# 2020_Circuit_Example_ArduinoUno_Version_.net
KiCad netlist of a schematic drawn in EAGLE
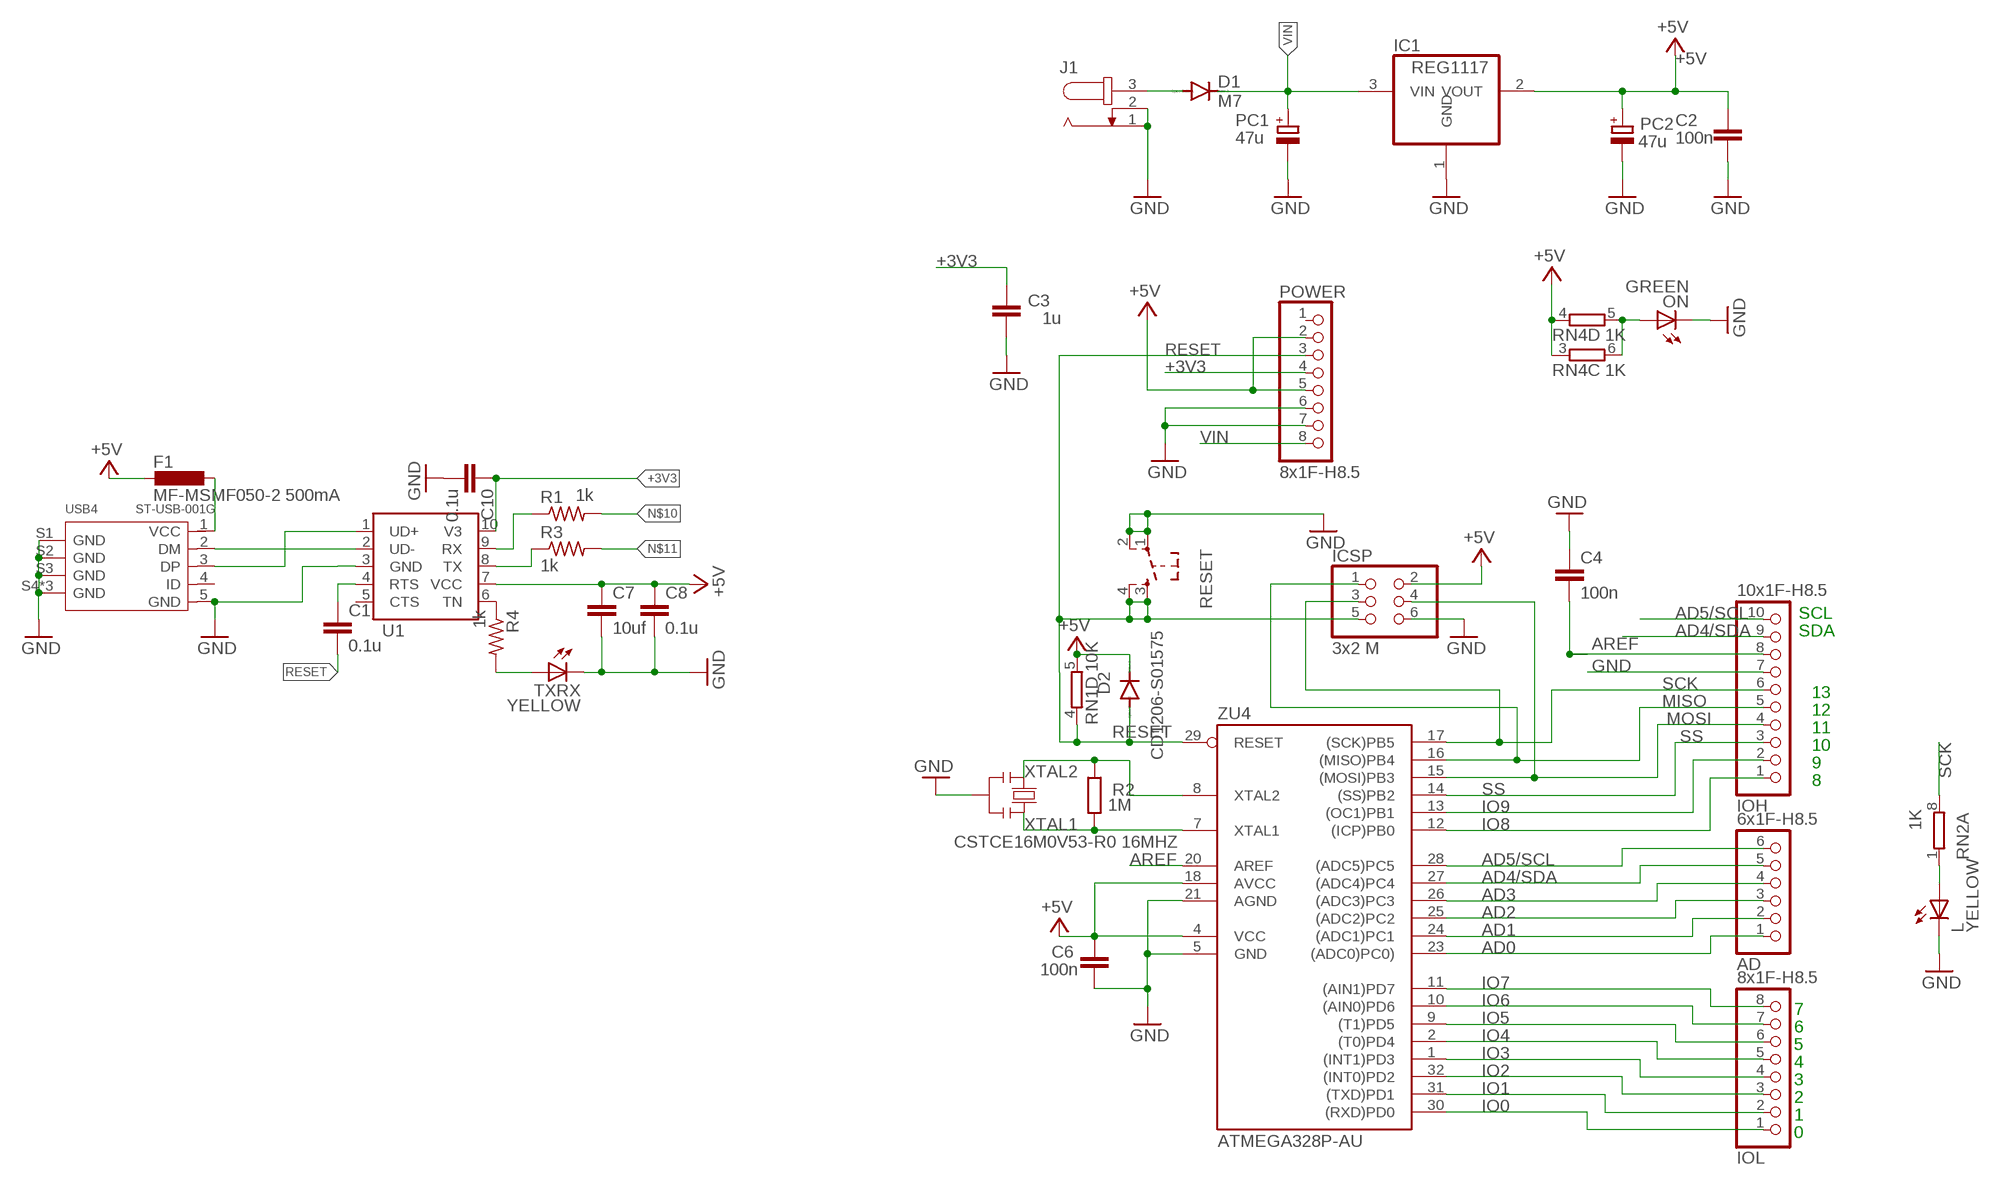
[diagram p0: schematic, sheet 1]

(export (version "E")
  (design (tool "Eeschema 10.0.6"))
  (components
    (comp (ref "AD")
      (value "6x1F-H8.5")
      (footprint "eagle-import:1X06")
      (libsource (lib "eagle-import") (part "PINHD-1X6"))
    )
    (comp (ref "C1")
      (value "0.1u")
      (footprint "eagle-import:C0805")
      (libsource (lib "eagle-import") (part "rcl_C-EUC0805"))
    )
    (comp (ref "C2")
      (value "100n")
      (footprint "eagle-import:C0603-ROUND")
      (libsource (lib "eagle-import") (part "C-EU0603-RND"))
    )
    (comp (ref "C3")
      (value "1u")
      (footprint "eagle-import:C0603-ROUND")
      (libsource (lib "eagle-import") (part "C-EU0603-RND"))
    )
    (comp (ref "C4")
      (value "100n")
      (footprint "eagle-import:C0805")
      (libsource (lib "eagle-import") (part "rcl_C-EUC0805"))
    )
    (comp (ref "C6")
      (value "100n")
      (footprint "eagle-import:C0603-ROUND")
      (libsource (lib "eagle-import") (part "C-EU0603-RND"))
    )
    (comp (ref "C7")
      (value "10uf")
      (footprint "eagle-import:C0805")
      (libsource (lib "eagle-import") (part "rcl_C-EUC0805"))
    )
    (comp (ref "C8")
      (value "0.1u")
      (footprint "eagle-import:C0805")
      (libsource (lib "eagle-import") (part "rcl_C-EUC0805"))
    )
    (comp (ref "C10")
      (value "0.1u")
      (footprint "eagle-import:C0805")
      (libsource (lib "eagle-import") (part "rcl_C-EUC0805"))
    )
    (comp (ref "D1")
      (value "M7")
      (footprint "eagle-import:SMB")
      (libsource (lib "eagle-import") (part "DIODE-SMB"))
    )
    (comp (ref "D2")
      (value "CD1206-S01575")
      (footprint "eagle-import:MINIMELF")
      (libsource (lib "eagle-import") (part "DIODE-MINIMELF"))
    )
    (comp (ref "F1")
      (value "MF-MSMF050-2 500mA")
      (footprint "eagle-import:L1812")
      (libsource (lib "eagle-import") (part "L-EUL1812"))
    )
    (comp (ref "IC1")
      (value "REG1117")
      (footprint "eagle-import:SOT223")
      (libsource (lib "eagle-import") (part "REG1117"))
    )
    (comp (ref "ICSP")
      (value "3x2 M")
      (footprint "eagle-import:2X03")
      (libsource (lib "eagle-import") (part "PINHD-2X3"))
    )
    (comp (ref "IOH")
      (value "10x1F-H8.5")
      (footprint "eagle-import:1X10")
      (libsource (lib "eagle-import") (part "PINHD-1X10_ARD"))
    )
    (comp (ref "IOL")
      (value "8x1F-H8.5")
      (footprint "eagle-import:1X08")
      (libsource (lib "eagle-import") (part "PINHD-1X8"))
    )
    (comp (ref "J1")
      (value "JACK-PLUG0")
      (footprint "eagle-import:SPC4077")
      (libsource (lib "eagle-import") (part "JACK-PLUG0"))
    )
    (comp (ref "L")
      (value "YELLOW")
      (footprint "eagle-import:CHIP-LED0805")
      (libsource (lib "eagle-import") (part "LEDCHIP-LED0805"))
    )
    (comp (ref "ON")
      (value "GREEN")
      (footprint "eagle-import:CHIP-LED0805")
      (libsource (lib "eagle-import") (part "LEDCHIP-LED0805"))
    )
    (comp (ref "PC1")
      (value "47u")
      (footprint "eagle-import:PANASONIC_D")
      (libsource (lib "eagle-import") (part "CPOL-EUD"))
    )
    (comp (ref "PC2")
      (value "47u")
      (footprint "eagle-import:PANASONIC_D")
      (libsource (lib "eagle-import") (part "CPOL-EUD"))
    )
    (comp (ref "POWER")
      (value "8x1F-H8.5")
      (footprint "eagle-import:1X08")
      (libsource (lib "eagle-import") (part "PINHD-1X8"))
    )
    (comp (ref "R1")
      (value "1k")
      (footprint "eagle-import:M0805")
      (libsource (lib "eagle-import") (part "R-US_M0805"))
    )
    (comp (ref "R2")
      (value "1M")
      (footprint "eagle-import:R0603-ROUND")
      (libsource (lib "eagle-import") (part "R-EU_R0603"))
    )
    (comp (ref "R3")
      (value "1k")
      (footprint "eagle-import:M0805")
      (libsource (lib "eagle-import") (part "R-US_M0805"))
    )
    (comp (ref "R4")
      (value "1k")
      (footprint "eagle-import:M0805")
      (libsource (lib "eagle-import") (part "R-US_M0805"))
    )
    (comp (ref "RESET")
      (value "SW_TACT_4P")
      (footprint "eagle-import:SW_TACT_SMALL")
      (libsource (lib "eagle-import") (part "SW_TACT_4P"))
    )
    (comp (ref "RN1")
      (value "10K")
      (footprint "eagle-import:CAY16")
      (libsource (lib "eagle-import") (part "4R-NCAY16"))
    )
    (comp (ref "RN2")
      (value "1K")
      (footprint "eagle-import:CAY16")
      (libsource (lib "eagle-import") (part "4R-NCAY16"))
    )
    (comp (ref "RN4")
      (value "1K")
      (footprint "eagle-import:CAY16")
      (libsource (lib "eagle-import") (part "4R-NCAY16"))
    )
    (comp (ref "TXRX")
      (value "YELLOW")
      (footprint "eagle-import:CHIP-LED0805")
      (libsource (lib "eagle-import") (part "LEDCHIP-LED0805"))
    )
    (comp (ref "U1")
      (value "CH340ESMD")
      (footprint "eagle-import:MSOP10")
      (libsource (lib "eagle-import") (part "CH340ESMD"))
    )
    (comp (ref "USB4")
      (value "ST-USB-001G")
      (footprint "eagle-import:MICRO-USB5+4P-SMD-0.65-B")
      (libsource (lib "eagle-import") (part "MICRO-USB-SMD-B-WITHOUT-POST-W/P(ST-USB-001G)"))
    )
    (comp (ref "Y2")
      (value "CSTCE16M0V53-R0 16MHZ")
      (footprint "eagle-import:RESONATOR")
      (libsource (lib "eagle-import") (part "RESONATORMU"))
    )
    (comp (ref "ZU4")
      (value "ATMEGA328P-AU")
      (footprint "eagle-import:TQFP32-08")
      (libsource (lib "eagle-import") (part "ATMEGA328P-AU"))
    )
  )
  (nets
    (net (code "1") (name "+3V3") (class "Default")
      (node (ref "C10") (pin "1") (pinfunction "1_1") (pintype "passive"))
      (node (ref "C3") (pin "2") (pinfunction "2_2") (pintype "passive"))
      (node (ref "POWER") (pin "4") (pinfunction "4_4") (pintype "passive"))
      (node (ref "U1") (pin "10") (pinfunction "V3_10") (pintype "power_in"))
    )
    (net (code "2") (name "+5V") (class "Default")
      (node (ref "C2") (pin "2") (pinfunction "2_2") (pintype "passive"))
      (node (ref "C6") (pin "2") (pinfunction "2_2") (pintype "passive"))
      (node (ref "C7") (pin "1") (pinfunction "1_1") (pintype "passive"))
      (node (ref "C8") (pin "1") (pinfunction "1_1") (pintype "passive"))
      (node (ref "D2") (pin "C") (pinfunction "C_C") (pintype "passive"))
      (node (ref "F1") (pin "2") (pinfunction "2_2") (pintype "passive"))
      (node (ref "IC1") (pin "2") (pinfunction "VOUT_2") (pintype "output"))
      (node (ref "ICSP") (pin "2") (pinfunction "2_2") (pintype "passive"))
      (node (ref "PC2") (pin "+") (pinfunction "+_+") (pintype "passive"))
      (node (ref "POWER") (pin "2") (pinfunction "2_2") (pintype "passive"))
      (node (ref "POWER") (pin "5") (pinfunction "5_5") (pintype "passive"))
      (node (ref "RN1") (pin "5") (pinfunction "2_5") (pintype "passive"))
      (node (ref "RN4") (pin "3") (pinfunction "1_3") (pintype "passive"))
      (node (ref "RN4") (pin "4") (pinfunction "1_4") (pintype "passive"))
      (node (ref "U1") (pin "7") (pinfunction "VCC_7") (pintype "power_in"))
      (node (ref "ZU4") (pin "18") (pinfunction "AVCC_18") (pintype "power_in"))
      (node (ref "ZU4") (pin "4") (pinfunction "VCC_4") (pintype "power_in"))
    )
    (net (code "3") (name "/AD0") (class "Default")
      (node (ref "AD") (pin "1") (pinfunction "1_1") (pintype "passive"))
      (node (ref "ZU4") (pin "23") (pinfunction "(ADC0)PC0)_23") (pintype "bidirectional"))
    )
    (net (code "4") (name "/AD1") (class "Default")
      (node (ref "AD") (pin "2") (pinfunction "2_2") (pintype "passive"))
      (node (ref "ZU4") (pin "24") (pinfunction "(ADC1)PC1_24") (pintype "bidirectional"))
    )
    (net (code "5") (name "/AD2") (class "Default")
      (node (ref "AD") (pin "3") (pinfunction "3_3") (pintype "passive"))
      (node (ref "ZU4") (pin "25") (pinfunction "(ADC2)PC2_25") (pintype "bidirectional"))
    )
    (net (code "6") (name "/AD3") (class "Default")
      (node (ref "AD") (pin "4") (pinfunction "4_4") (pintype "passive"))
      (node (ref "ZU4") (pin "26") (pinfunction "(ADC3)PC3_26") (pintype "bidirectional"))
    )
    (net (code "7") (name "/AD4{slash}SDA") (class "Default")
      (node (ref "AD") (pin "5") (pinfunction "5_5") (pintype "passive"))
      (node (ref "IOH") (pin "9") (pinfunction "9_9") (pintype "passive"))
      (node (ref "ZU4") (pin "27") (pinfunction "(ADC4)PC4_27") (pintype "bidirectional"))
    )
    (net (code "8") (name "/AD5{slash}SCL") (class "Default")
      (node (ref "AD") (pin "6") (pinfunction "6_6") (pintype "passive"))
      (node (ref "IOH") (pin "10") (pinfunction "10_10") (pintype "passive"))
      (node (ref "ZU4") (pin "28") (pinfunction "(ADC5)PC5_28") (pintype "bidirectional"))
    )
    (net (code "9") (name "/AREF") (class "Default")
      (node (ref "C4") (pin "2") (pinfunction "2_2") (pintype "passive"))
      (node (ref "IOH") (pin "8") (pinfunction "8_8") (pintype "passive"))
      (node (ref "ZU4") (pin "20") (pinfunction "AREF_20") (pintype "passive"))
    )
    (net (code "10") (name "/IO0") (class "Default")
      (node (ref "IOL") (pin "1") (pinfunction "1_1") (pintype "passive"))
      (node (ref "ZU4") (pin "30") (pinfunction "(RXD)PD0_30") (pintype "bidirectional"))
    )
    (net (code "11") (name "/IO1") (class "Default")
      (node (ref "IOL") (pin "2") (pinfunction "2_2") (pintype "passive"))
      (node (ref "ZU4") (pin "31") (pinfunction "(TXD)PD1_31") (pintype "bidirectional"))
    )
    (net (code "12") (name "/IO2") (class "Default")
      (node (ref "IOL") (pin "3") (pinfunction "3_3") (pintype "passive"))
      (node (ref "ZU4") (pin "32") (pinfunction "(INT0)PD2_32") (pintype "bidirectional"))
    )
    (net (code "13") (name "/IO3") (class "Default")
      (node (ref "IOL") (pin "4") (pinfunction "4_4") (pintype "passive"))
      (node (ref "ZU4") (pin "1") (pinfunction "(INT1)PD3_1") (pintype "bidirectional"))
    )
    (net (code "14") (name "/IO4") (class "Default")
      (node (ref "IOL") (pin "5") (pinfunction "5_5") (pintype "passive"))
      (node (ref "ZU4") (pin "2") (pinfunction "(T0)PD4_2") (pintype "bidirectional"))
    )
    (net (code "15") (name "/IO5") (class "Default")
      (node (ref "IOL") (pin "6") (pinfunction "6_6") (pintype "passive"))
      (node (ref "ZU4") (pin "9") (pinfunction "(T1)PD5_9") (pintype "bidirectional"))
    )
    (net (code "16") (name "/IO6") (class "Default")
      (node (ref "IOL") (pin "7") (pinfunction "7_7") (pintype "passive"))
      (node (ref "ZU4") (pin "10") (pinfunction "(AIN0)PD6_10") (pintype "bidirectional"))
    )
    (net (code "17") (name "/IO7") (class "Default")
      (node (ref "IOL") (pin "8") (pinfunction "8_8") (pintype "passive"))
      (node (ref "ZU4") (pin "11") (pinfunction "(AIN1)PD7_11") (pintype "bidirectional"))
    )
    (net (code "18") (name "/IO8") (class "Default")
      (node (ref "IOH") (pin "1") (pinfunction "1_1") (pintype "passive"))
      (node (ref "ZU4") (pin "12") (pinfunction "(ICP)PB0_12") (pintype "bidirectional"))
    )
    (net (code "19") (name "/IO9") (class "Default")
      (node (ref "IOH") (pin "2") (pinfunction "2_2") (pintype "passive"))
      (node (ref "ZU4") (pin "13") (pinfunction "(OC1)PB1_13") (pintype "bidirectional"))
    )
    (net (code "20") (name "/MISO") (class "Default")
      (node (ref "ICSP") (pin "1") (pinfunction "1_1") (pintype "passive"))
      (node (ref "IOH") (pin "5") (pinfunction "5_5") (pintype "passive"))
      (node (ref "ZU4") (pin "16") (pinfunction "(MISO)PB4_16") (pintype "bidirectional"))
    )
    (net (code "21") (name "/MOSI") (class "Default")
      (node (ref "ICSP") (pin "4") (pinfunction "4_4") (pintype "passive"))
      (node (ref "IOH") (pin "4") (pinfunction "4_4") (pintype "passive"))
      (node (ref "ZU4") (pin "15") (pinfunction "(MOSI)PB3_15") (pintype "bidirectional"))
    )
    (net (code "22") (name "/SCK") (class "Default")
      (node (ref "ICSP") (pin "3") (pinfunction "3_3") (pintype "passive"))
      (node (ref "IOH") (pin "6") (pinfunction "6_6") (pintype "passive"))
      (node (ref "RN2") (pin "8") (pinfunction "2_8") (pintype "passive"))
      (node (ref "ZU4") (pin "17") (pinfunction "(SCK)PB5_17") (pintype "bidirectional"))
    )
    (net (code "23") (name "/SS") (class "Default")
      (node (ref "IOH") (pin "3") (pinfunction "3_3") (pintype "passive"))
      (node (ref "ZU4") (pin "14") (pinfunction "(SS)PB2_14") (pintype "bidirectional"))
    )
    (net (code "24") (name "/XTAL1") (class "Default")
      (node (ref "R2") (pin "1") (pinfunction "1_1") (pintype "passive"))
      (node (ref "Y2") (pin "3") (pinfunction "3_3") (pintype "passive"))
      (node (ref "ZU4") (pin "7") (pinfunction "XTAL1_7") (pintype "bidirectional"))
    )
    (net (code "25") (name "/XTAL2") (class "Default")
      (node (ref "R2") (pin "2") (pinfunction "2_2") (pintype "passive"))
      (node (ref "Y2") (pin "1") (pinfunction "1_1") (pintype "passive"))
      (node (ref "ZU4") (pin "8") (pinfunction "XTAL2_8") (pintype "bidirectional"))
    )
    (net (code "26") (name "GND") (class "Default")
      (node (ref "C10") (pin "2") (pinfunction "2_2") (pintype "passive"))
      (node (ref "C2") (pin "1") (pinfunction "1_1") (pintype "passive"))
      (node (ref "C3") (pin "1") (pinfunction "1_1") (pintype "passive"))
      (node (ref "C4") (pin "1") (pinfunction "1_1") (pintype "passive"))
      (node (ref "C6") (pin "1") (pinfunction "1_1") (pintype "passive"))
      (node (ref "C7") (pin "2") (pinfunction "2_2") (pintype "passive"))
      (node (ref "C8") (pin "2") (pinfunction "2_2") (pintype "passive"))
      (node (ref "IC1") (pin "1") (pinfunction "GND_1") (pintype "power_in"))
      (node (ref "ICSP") (pin "6") (pinfunction "6_6") (pintype "passive"))
      (node (ref "IOH") (pin "7") (pinfunction "7_7") (pintype "passive"))
      (node (ref "J1") (pin "1") (pinfunction "1_1") (pintype "passive"))
      (node (ref "J1") (pin "2") (pinfunction "2_2") (pintype "passive"))
      (node (ref "L") (pin "C") (pinfunction "C_C") (pintype "passive"))
      (node (ref "ON") (pin "C") (pinfunction "C_C") (pintype "passive"))
      (node (ref "PC1") (pin "-") (pinfunction "-_-") (pintype "passive"))
      (node (ref "PC2") (pin "-") (pinfunction "-_-") (pintype "passive"))
      (node (ref "POWER") (pin "6") (pinfunction "6_6") (pintype "passive"))
      (node (ref "POWER") (pin "7") (pinfunction "7_7") (pintype "passive"))
      (node (ref "RESET") (pin "1") (pinfunction "1_1") (pintype "passive"))
      (node (ref "RESET") (pin "2") (pinfunction "2_2") (pintype "passive"))
      (node (ref "TXRX") (pin "C") (pinfunction "C_C") (pintype "passive"))
      (node (ref "U1") (pin "3") (pinfunction "GND_3") (pintype "power_in"))
      (node (ref "USB4") (pin "5") (pinfunction "GND_5") (pintype "bidirectional"))
      (node (ref "USB4") (pin "S1") (pinfunction "GND_S1") (pintype "bidirectional"))
      (node (ref "USB4") (pin "S2") (pinfunction "GND_S2") (pintype "bidirectional"))
      (node (ref "USB4") (pin "S3") (pinfunction "GND_S3") (pintype "bidirectional"))
      (node (ref "USB4") (pin "S4") (pinfunction "GND_S4") (pintype "bidirectional"))
      (node (ref "USB4") (pin "S5") (pinfunction "GND_S5") (pintype "bidirectional"))
      (node (ref "USB4") (pin "S6") (pinfunction "GND_S6") (pintype "bidirectional"))
      (node (ref "Y2") (pin "2") (pinfunction "2_2") (pintype "passive"))
      (node (ref "ZU4") (pin "21") (pinfunction "AGND_21") (pintype "power_in"))
      (node (ref "ZU4") (pin "5") (pinfunction "GND_5") (pintype "power_in"))
    )
    (net (code "27") (name "N$10") (class "Default")
      (node (ref "R1") (pin "2") (pinfunction "2_2") (pintype "passive"))
    )
    (net (code "28") (name "N$11") (class "Default")
      (node (ref "R3") (pin "2") (pinfunction "2_2") (pintype "passive"))
    )
    (net (code "29") (name "Net-(D1-PadA)") (class "Default")
      (node (ref "D1") (pin "A") (pinfunction "A_A") (pintype "passive"))
      (node (ref "J1") (pin "3") (pinfunction "3_3") (pintype "passive"))
    )
    (net (code "30") (name "Net-(L-PadA)") (class "Default")
      (node (ref "L") (pin "A") (pinfunction "A_A") (pintype "passive"))
      (node (ref "RN2") (pin "1") (pinfunction "1_1") (pintype "passive"))
    )
    (net (code "31") (name "Net-(R4-Pad2)") (class "Default")
      (node (ref "R4") (pin "2") (pinfunction "2_2") (pintype "passive"))
      (node (ref "TXRX") (pin "A") (pinfunction "A_A") (pintype "passive"))
    )
    (net (code "32") (name "Net-(RN4C-2)") (class "Default")
      (node (ref "ON") (pin "A") (pinfunction "A_A") (pintype "passive"))
      (node (ref "RN4") (pin "5") (pinfunction "2_5") (pintype "passive"))
      (node (ref "RN4") (pin "6") (pinfunction "2_6") (pintype "passive"))
    )
    (net (code "33") (name "Net-(U1-RTS)") (class "Default")
      (node (ref "C1") (pin "1") (pinfunction "1_1") (pintype "passive"))
      (node (ref "U1") (pin "4") (pinfunction "RTS_4") (pintype "output"))
    )
    (net (code "34") (name "Net-(U1-RX)") (class "Default")
      (node (ref "R1") (pin "1") (pinfunction "1_1") (pintype "passive"))
      (node (ref "U1") (pin "9") (pinfunction "RX_9") (pintype "input"))
    )
    (net (code "35") (name "Net-(U1-TN)") (class "Default")
      (node (ref "R4") (pin "1") (pinfunction "1_1") (pintype "passive"))
      (node (ref "U1") (pin "6") (pinfunction "TN_6") (pintype "output"))
    )
    (net (code "36") (name "Net-(U1-TX)") (class "Default")
      (node (ref "R3") (pin "1") (pinfunction "1_1") (pintype "passive"))
      (node (ref "U1") (pin "8") (pinfunction "TX_8") (pintype "output"))
    )
    (net (code "37") (name "Net-(U1-UD+)") (class "Default")
      (node (ref "U1") (pin "1") (pinfunction "UD+_1") (pintype "bidirectional"))
      (node (ref "USB4") (pin "3") (pinfunction "DP_3") (pintype "bidirectional"))
    )
    (net (code "38") (name "Net-(U1-UD-)") (class "Default")
      (node (ref "U1") (pin "2") (pinfunction "UD-_2") (pintype "bidirectional"))
      (node (ref "USB4") (pin "2") (pinfunction "DM_2") (pintype "bidirectional"))
    )
    (net (code "39") (name "Net-(USB4-VCC)") (class "Default")
      (node (ref "F1") (pin "1") (pinfunction "1_1") (pintype "passive"))
      (node (ref "USB4") (pin "1") (pinfunction "VCC_1") (pintype "bidirectional"))
    )
    (net (code "40") (name "RESET") (class "Default")
      (node (ref "C1") (pin "2") (pinfunction "2_2") (pintype "passive"))
      (node (ref "D2") (pin "A") (pinfunction "A_A") (pintype "passive"))
      (node (ref "ICSP") (pin "5") (pinfunction "5_5") (pintype "passive"))
      (node (ref "POWER") (pin "3") (pinfunction "3_3") (pintype "passive"))
      (node (ref "RESET") (pin "3") (pinfunction "3_3") (pintype "passive"))
      (node (ref "RESET") (pin "4") (pinfunction "4_4") (pintype "passive"))
      (node (ref "RN1") (pin "4") (pinfunction "1_4") (pintype "passive"))
      (node (ref "ZU4") (pin "29") (pinfunction "RESET_29") (pintype "input"))
    )
    (net (code "41") (name "VIN") (class "Default")
      (node (ref "D1") (pin "C") (pinfunction "C_C") (pintype "passive"))
      (node (ref "IC1") (pin "3") (pinfunction "VIN_3") (pintype "input"))
      (node (ref "PC1") (pin "+") (pinfunction "+_+") (pintype "passive"))
      (node (ref "POWER") (pin "8") (pinfunction "8_8") (pintype "passive"))
    )
    (net (code "42") (name "unconnected-(POWER-Pad1)") (class "Default")
      (node (ref "POWER") (pin "1") (pinfunction "1_1") (pintype "passive"))
    )
    (net (code "43") (name "unconnected-(U1-CTS-Pad5)") (class "Default")
      (node (ref "U1") (pin "5") (pinfunction "CTS_5") (pintype "input"))
    )
    (net (code "44") (name "unconnected-(USB4-ID-Pad4)") (class "Default")
      (node (ref "USB4") (pin "4") (pinfunction "ID_4") (pintype "bidirectional"))
    )
  )
)
